# Gimbal-Breakout.net
KiCad netlist of a schematic drawn in EAGLE
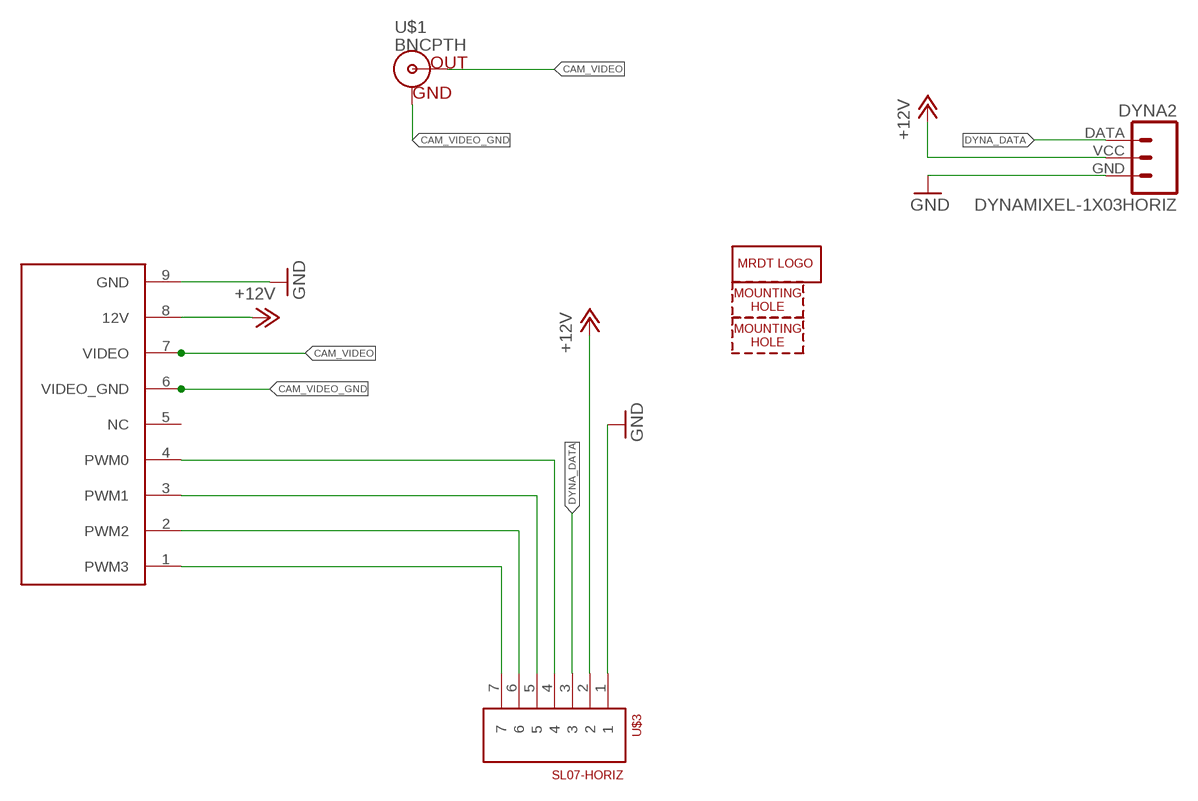
[diagram p0: schematic, sheet 1]

(export (version "E")
  (design (tool "Eeschema 10.0.6"))
  (components
    (comp (ref "DYNA2")
      (value "DYNAMIXEL-1X03HORIZ")
      (footprint "eagle-import:MLX-SPOX5268-3PIN")
      (fields (field (name "MFR") "Molex"))
      (libsource (lib "eagle-import") (part "DYNAMIXEL-1X03HORIZ"))
    )
    (comp (ref "H1")
      (value "MOUNTING_HOLE#4")
      (footprint "eagle-import:#4_SCREW")
      (libsource (lib "eagle-import") (part "MOUNTING_HOLE#4"))
    )
    (comp (ref "H2")
      (value "MOUNTING_HOLE#4")
      (footprint "eagle-import:#4_SCREW")
      (libsource (lib "eagle-import") (part "MOUNTING_HOLE#4"))
    )
    (comp (ref "LOGO1")
      (value "MRDT_LOGO")
      (footprint "eagle-import:MRDT_LOGO")
      (libsource (lib "eagle-import") (part "MRDT_LOGO"))
    )
    (comp (ref "U$1")
      (value "BNCPTH")
      (footprint "eagle-import:BNC")
      (libsource (lib "eagle-import") (part "BNCPTH"))
    )
    (comp (ref "U$3")
      (value "SL07-HORIZ")
      (footprint "eagle-import:MOLEX-70551-0006")
      (libsource (lib "eagle-import") (part "SL07-HORIZ"))
    )
    (comp (ref "U$4")
      (value "CAMERA_BREAKOUT")
      (footprint "eagle-import:CAM_CONNECTOR")
      (libsource (lib "eagle-import") (part "CAMERA_BREAKOUT"))
    )
  )
  (nets
    (net (code "1") (name "+12V") (class "Default")
      (node (ref "DYNA2") (pin "VCC") (pinfunction "VCC_VCC") (pintype "passive"))
      (node (ref "U$3") (pin "2") (pinfunction "2_2") (pintype "bidirectional"))
      (node (ref "U$4") (pin "8") (pinfunction "12V_8") (pintype "bidirectional"))
    )
    (net (code "2") (name "CAM_VIDEO") (class "Default")
      (node (ref "U$1") (pin "S") (pinfunction "OUT_S") (pintype "bidirectional"))
      (node (ref "U$4") (pin "7") (pinfunction "VIDEO_7") (pintype "bidirectional"))
    )
    (net (code "3") (name "CAM_VIDEO_GND") (class "Default")
      (node (ref "U$1") (pin "GND") (pinfunction "GND_GND") (pintype "bidirectional"))
      (node (ref "U$4") (pin "6") (pinfunction "VIDEO_GND_6") (pintype "bidirectional"))
    )
    (net (code "4") (name "DYNA_DATA") (class "Default")
      (node (ref "DYNA2") (pin "DATA") (pinfunction "DATA_DATA") (pintype "passive"))
      (node (ref "U$3") (pin "3") (pinfunction "3_3") (pintype "bidirectional"))
    )
    (net (code "5") (name "GND") (class "Default")
      (node (ref "DYNA2") (pin "GND") (pinfunction "GND_GND") (pintype "passive"))
      (node (ref "U$3") (pin "1") (pinfunction "1_1") (pintype "bidirectional"))
      (node (ref "U$4") (pin "9") (pinfunction "GND_9") (pintype "bidirectional"))
    )
    (net (code "6") (name "Net-(U$4-PWM0)") (class "Default")
      (node (ref "U$3") (pin "4") (pinfunction "4_4") (pintype "bidirectional"))
      (node (ref "U$4") (pin "4") (pinfunction "PWM0_4") (pintype "bidirectional"))
    )
    (net (code "7") (name "Net-(U$4-PWM1)") (class "Default")
      (node (ref "U$3") (pin "5") (pinfunction "5_5") (pintype "bidirectional"))
      (node (ref "U$4") (pin "3") (pinfunction "PWM1_3") (pintype "bidirectional"))
    )
    (net (code "8") (name "Net-(U$4-PWM2)") (class "Default")
      (node (ref "U$3") (pin "6") (pinfunction "6_6") (pintype "bidirectional"))
      (node (ref "U$4") (pin "2") (pinfunction "PWM2_2") (pintype "bidirectional"))
    )
    (net (code "9") (name "Net-(U$4-PWM3)") (class "Default")
      (node (ref "U$3") (pin "7") (pinfunction "7_7") (pintype "bidirectional"))
      (node (ref "U$4") (pin "1") (pinfunction "PWM3_1") (pintype "bidirectional"))
    )
    (net (code "10") (name "unconnected-(U$4-NC-Pad5)") (class "Default")
      (node (ref "U$4") (pin "5") (pinfunction "NC_5") (pintype "bidirectional"))
    )
  )
)
